# mclon_nano_0_0001.net
KiCad netlist of a schematic drawn in EAGLE
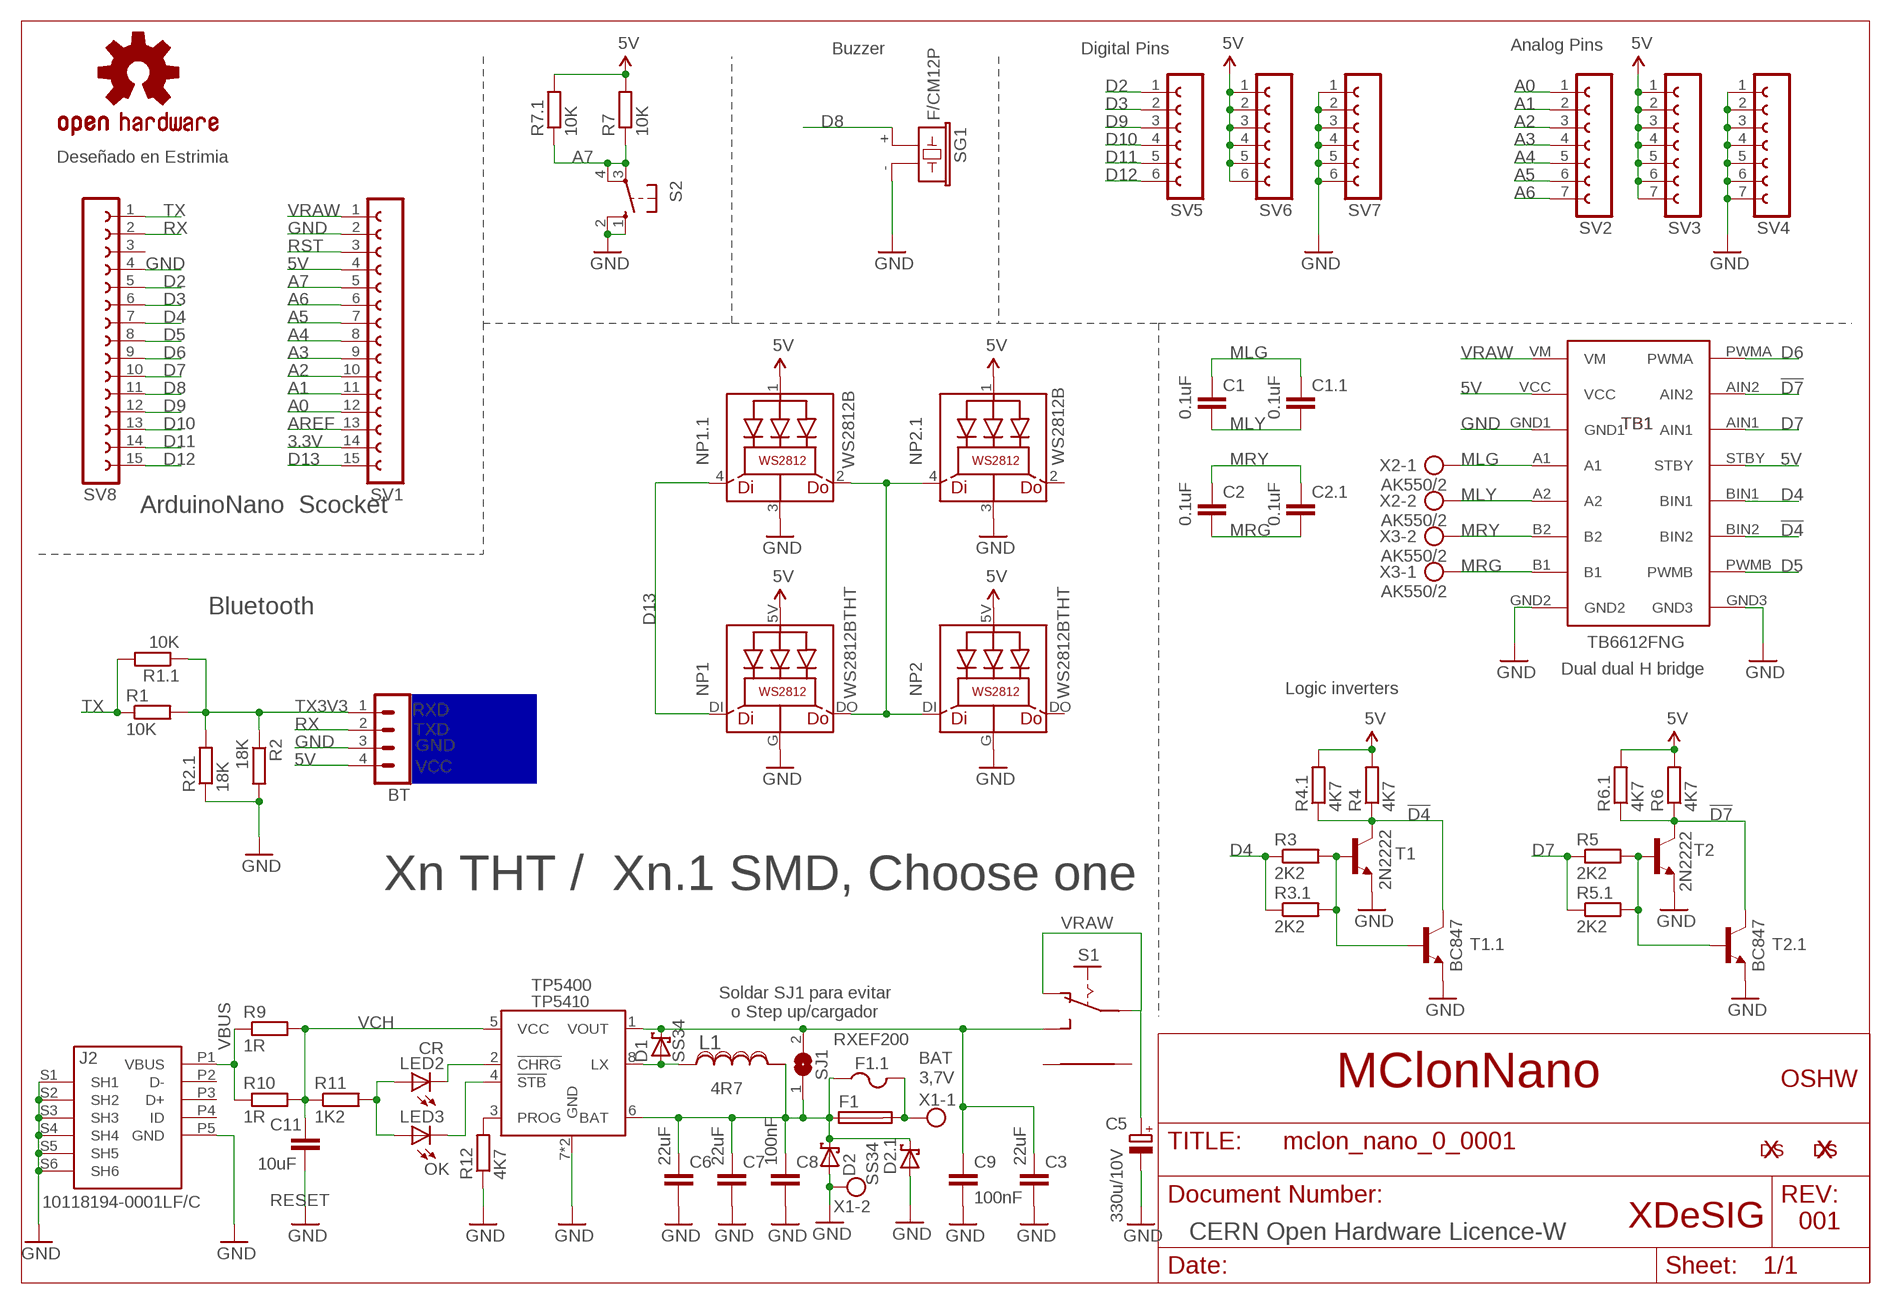
[diagram p0: schematic, sheet 1]

(export (version "E")
  (design (tool "Eeschema 10.0.6"))
  (components
    (comp (ref "BT")
      (value "MA04-1")
      (footprint "eagle-import:MA04-1")
      (libsource (lib "eagle-import") (part "MA04-1"))
    )
    (comp (ref "C1")
      (value "0.1uF")
      (footprint "eagle-import:C050-024X044")
      (libsource (lib "eagle-import") (part "C-EU050-024X044"))
    )
    (comp (ref "C1.1")
      (value "0.1uF")
      (footprint "eagle-import:C1206")
      (libsource (lib "eagle-import") (part "C-EUC1206"))
    )
    (comp (ref "C2")
      (value "0.1uF")
      (footprint "eagle-import:C050-024X044")
      (libsource (lib "eagle-import") (part "C-EU050-024X044"))
    )
    (comp (ref "C2.1")
      (value "0.1uF")
      (footprint "eagle-import:C1206")
      (libsource (lib "eagle-import") (part "C-EUC1206"))
    )
    (comp (ref "C3")
      (value "22uF")
      (footprint "eagle-import:C1206")
      (libsource (lib "eagle-import") (part "C-EUC1206"))
    )
    (comp (ref "C5")
      (value "330u/10V")
      (footprint "eagle-import:E2,5-6")
      (libsource (lib "eagle-import") (part "CPOL-EUE2.5-6"))
    )
    (comp (ref "C6")
      (value "22uF")
      (footprint "eagle-import:C1206")
      (libsource (lib "eagle-import") (part "C-EUC1206"))
    )
    (comp (ref "C7")
      (value "22uF")
      (footprint "eagle-import:C1206")
      (libsource (lib "eagle-import") (part "C-EUC1206"))
    )
    (comp (ref "C8")
      (value "100nF")
      (footprint "eagle-import:C1206")
      (libsource (lib "eagle-import") (part "C-EUC1206"))
    )
    (comp (ref "C9")
      (value "100nF")
      (footprint "eagle-import:C1206")
      (libsource (lib "eagle-import") (part "C-EUC1206"))
    )
    (comp (ref "C11")
      (value "10uF")
      (footprint "eagle-import:C1206")
      (libsource (lib "eagle-import") (part "C-EUC1206"))
    )
    (comp (ref "D1")
      (value "SS34")
      (footprint "eagle-import:DIODE_SMA")
      (libsource (lib "eagle-import") (part "DIODE_SCHOTTKY-DIODESMA"))
    )
    (comp (ref "D2")
      (value "SS34")
      (footprint "eagle-import:DIODE_SMA")
      (libsource (lib "eagle-import") (part "DIODE_SCHOTTKY-DIODESMA"))
    )
    (comp (ref "D2.1")
      (value "SCHOTTKY-DIODEDO35-7")
      (footprint "eagle-import:DO35-7")
      (libsource (lib "eagle-import") (part "SCHOTTKY-DIODEDO35-7"))
    )
    (comp (ref "F1")
      (value "RXEF200")
      (footprint "eagle-import:TE5")
      (libsource (lib "eagle-import") (part "FUSETE5"))
    )
    (comp (ref "F1.1")
      (value "MF-NSMF200")
      (footprint "eagle-import:1812")
      (libsource (lib "eagle-import") (part "PTCFUSE-1812"))
    )
    (comp (ref "J2")
      (value "10118194-0001LF/C")
      (footprint "eagle-import:SMARTPRJ_CON2_USB_MICRO_B_AT")
      (libsource (lib "eagle-import") (part "SMARTPRJ_MYCON2_USB-MINI-B"))
    )
    (comp (ref "L1")
      (value "4R7")
      (footprint "eagle-import:SRN6045")
      (fields (field (name "MF") "Bourns") (field (name "MP") "SRN6045-330M"))
      (libsource (lib "eagle-import") (part "SRN6045-330M6045"))
    )
    (comp (ref "LED2")
      (value "CR")
      (footprint "eagle-import:CHIPLED_0805")
      (libsource (lib "eagle-import") (part "LEDCHIPLED_0805"))
    )
    (comp (ref "LED3")
      (value "OK")
      (footprint "eagle-import:CHIPLED_0805")
      (libsource (lib "eagle-import") (part "LEDCHIPLED_0805"))
    )
    (comp (ref "LOGO4")
      (value "OSHW-LOGOS")
      (footprint "eagle-import:OSHW-LOGO-S")
      (libsource (lib "eagle-import") (part "OSHW-LOGOS"))
    )
    (comp (ref "NP1")
      (value "WS2812BTHT")
      (footprint "eagle-import:NEOPIXEL5MM")
      (libsource (lib "eagle-import") (part "WS2812BTHT"))
    )
    (comp (ref "NP1.1")
      (value "WS2812B")
      (footprint "eagle-import:5050-4")
      (libsource (lib "eagle-import") (part "WS2812B"))
    )
    (comp (ref "NP2")
      (value "WS2812BTHT")
      (footprint "eagle-import:NEOPIXEL5MM")
      (libsource (lib "eagle-import") (part "WS2812BTHT"))
    )
    (comp (ref "NP2.1")
      (value "WS2812B")
      (footprint "eagle-import:5050-4")
      (libsource (lib "eagle-import") (part "WS2812B"))
    )
    (comp (ref "R1")
      (value "10K")
      (footprint "eagle-import:0204_7")
      (libsource (lib "eagle-import") (part "R-EU_0204/7"))
    )
    (comp (ref "R1.1")
      (value "10K")
      (footprint "eagle-import:R1206")
      (libsource (lib "eagle-import") (part "R-EU_R1206"))
    )
    (comp (ref "R2")
      (value "18K")
      (footprint "eagle-import:0204_7")
      (libsource (lib "eagle-import") (part "R-EU_0204/7"))
    )
    (comp (ref "R2.1")
      (value "18K")
      (footprint "eagle-import:R1206")
      (libsource (lib "eagle-import") (part "R-EU_R1206"))
    )
    (comp (ref "R3")
      (value "2K2")
      (footprint "eagle-import:0204_7")
      (libsource (lib "eagle-import") (part "R-EU_0204/7"))
    )
    (comp (ref "R3.1")
      (value "2K2")
      (footprint "eagle-import:R1206")
      (libsource (lib "eagle-import") (part "R-EU_R1206"))
    )
    (comp (ref "R4")
      (value "4K7")
      (footprint "eagle-import:0204_7")
      (libsource (lib "eagle-import") (part "R-EU_0204/7"))
    )
    (comp (ref "R4.1")
      (value "4K7")
      (footprint "eagle-import:R1206")
      (libsource (lib "eagle-import") (part "R-EU_R1206"))
    )
    (comp (ref "R5")
      (value "2K2")
      (footprint "eagle-import:0204_7")
      (libsource (lib "eagle-import") (part "R-EU_0204/7"))
    )
    (comp (ref "R5.1")
      (value "2K2")
      (footprint "eagle-import:R1206")
      (libsource (lib "eagle-import") (part "R-EU_R1206"))
    )
    (comp (ref "R6")
      (value "4K7")
      (footprint "eagle-import:0204_7")
      (libsource (lib "eagle-import") (part "R-EU_0204/7"))
    )
    (comp (ref "R6.1")
      (value "4K7")
      (footprint "eagle-import:R1206")
      (libsource (lib "eagle-import") (part "R-EU_R1206"))
    )
    (comp (ref "R7")
      (value "10K")
      (footprint "eagle-import:0204_7")
      (libsource (lib "eagle-import") (part "R-EU_0204/7"))
    )
    (comp (ref "R7.1")
      (value "10K")
      (footprint "eagle-import:R1206")
      (libsource (lib "eagle-import") (part "R-EU_R1206"))
    )
    (comp (ref "R9")
      (value "1R")
      (footprint "eagle-import:M1206")
      (libsource (lib "eagle-import") (part "R-EU_M1206"))
    )
    (comp (ref "R10")
      (value "1R")
      (footprint "eagle-import:M1206")
      (libsource (lib "eagle-import") (part "R-EU_M1206"))
    )
    (comp (ref "R11")
      (value "1K2")
      (footprint "eagle-import:R1206")
      (libsource (lib "eagle-import") (part "R-EU_R1206"))
    )
    (comp (ref "R12")
      (value "4K7")
      (footprint "eagle-import:R1206")
      (libsource (lib "eagle-import") (part "R-EU_R1206"))
    )
    (comp (ref "S1")
      (value "ESCORNA_SK12F14D")
      (footprint "eagle-import:ESCORNA_SK-12D07")
      (libsource (lib "eagle-import") (part "ESCORNA_SK12F14D"))
    )
    (comp (ref "S2")
      (value "10-XX")
      (footprint "eagle-import:B3F-10XX")
      (fields (field (name "MPN") "B3F-1000"))
      (libsource (lib "eagle-import") (part "10-XX"))
    )
    (comp (ref "SG1")
      (value "F/CM12P")
      (footprint "eagle-import:F_CM12P")
      (libsource (lib "eagle-import") (part "F/CM12P"))
    )
    (comp (ref "SJ1")
      (value "JUMPER_SJW")
      (footprint "eagle-import:JUMPER_SJW")
      (libsource (lib "eagle-import") (part "JUMPER_SJW"))
    )
    (comp (ref "SV1")
      (value "CON-LSTA_FE15-1")
      (footprint "eagle-import:CON-LSTA_FE15")
      (libsource (lib "eagle-import") (part "CON-LSTA_FE15-1"))
    )
    (comp (ref "SV2")
      (value "FE07-1")
      (footprint "eagle-import:FE07")
      (libsource (lib "eagle-import") (part "FE07-1"))
    )
    (comp (ref "SV3")
      (value "FE07-1")
      (footprint "eagle-import:FE07")
      (libsource (lib "eagle-import") (part "FE07-1"))
    )
    (comp (ref "SV4")
      (value "FE07-1")
      (footprint "eagle-import:FE07")
      (libsource (lib "eagle-import") (part "FE07-1"))
    )
    (comp (ref "SV5")
      (value "FE06-1")
      (footprint "eagle-import:FE06")
      (libsource (lib "eagle-import") (part "FE06-1"))
    )
    (comp (ref "SV6")
      (value "FE06-1")
      (footprint "eagle-import:FE06")
      (libsource (lib "eagle-import") (part "FE06-1"))
    )
    (comp (ref "SV7")
      (value "FE06-1")
      (footprint "eagle-import:FE06")
      (libsource (lib "eagle-import") (part "FE06-1"))
    )
    (comp (ref "SV8")
      (value "CON-LSTA_FE15-1")
      (footprint "eagle-import:CON-LSTA_FE15")
      (libsource (lib "eagle-import") (part "CON-LSTA_FE15-1"))
    )
    (comp (ref "T1")
      (value "2N2222")
      (footprint "eagle-import:TO92-EBC-OVAL")
      (libsource (lib "eagle-import") (part "2N2222"))
    )
    (comp (ref "T1.1")
      (value "BC847")
      (footprint "eagle-import:SOT23")
      (libsource (lib "eagle-import") (part "BC847"))
    )
    (comp (ref "T2")
      (value "2N2222")
      (footprint "eagle-import:TO92-EBC-OVAL")
      (libsource (lib "eagle-import") (part "2N2222"))
    )
    (comp (ref "T2.1")
      (value "BC847")
      (footprint "eagle-import:SOT23")
      (libsource (lib "eagle-import") (part "BC847"))
    )
    (comp (ref "TB1")
      (value "TB6612FNG")
      (footprint "eagle-import:TB6612FNG")
      (libsource (lib "eagle-import") (part "TB6612FNG"))
    )
    (comp (ref "U$7")
      (value "OSHW")
      (footprint "eagle-import:OSHW")
      (libsource (lib "eagle-import") (part "OSHW"))
    )
    (comp (ref "U$8")
      (value "XDESIG5MM")
      (footprint "eagle-import:XDESIG_CU")
      (libsource (lib "eagle-import") (part "XDESIG5MM"))
    )
    (comp (ref "U$18")
      (value "XDESIG21")
      (footprint "eagle-import:XDESIG")
      (libsource (lib "eagle-import") (part "XDESIG21"))
    )
    (comp (ref "U$19")
      (value "XDESIG5MM")
      (footprint "eagle-import:XDESIG_CU")
      (libsource (lib "eagle-import") (part "XDESIG5MM"))
    )
    (comp (ref "U1")
      (value "TP5400")
      (footprint "eagle-import:ESOP8")
      (libsource (lib "eagle-import") (part "TP5400"))
    )
    (comp (ref "X1")
      (value "AK550/2")
      (footprint "eagle-import:AK550_2")
      (libsource (lib "eagle-import") (part "AK550/2"))
    )
    (comp (ref "X2")
      (value "AK550/2")
      (footprint "eagle-import:AK550_2")
      (libsource (lib "eagle-import") (part "AK550/2"))
    )
    (comp (ref "X3")
      (value "AK550/2")
      (footprint "eagle-import:AK550_2")
      (libsource (lib "eagle-import") (part "AK550/2"))
    )
  )
  (nets
    (net (code "1") (name "/3.3V") (class "Default")
      (node (ref "SV1") (pin "14") (pinfunction "14_14") (pintype "passive"))
    )
    (net (code "2") (name "/A0") (class "Default")
      (node (ref "SV1") (pin "12") (pinfunction "12_12") (pintype "passive"))
      (node (ref "SV2") (pin "1") (pinfunction "1_1") (pintype "passive"))
    )
    (net (code "3") (name "/A1") (class "Default")
      (node (ref "SV1") (pin "11") (pinfunction "11_11") (pintype "passive"))
      (node (ref "SV2") (pin "2") (pinfunction "2_2") (pintype "passive"))
    )
    (net (code "4") (name "/A2") (class "Default")
      (node (ref "SV1") (pin "10") (pinfunction "10_10") (pintype "passive"))
      (node (ref "SV2") (pin "3") (pinfunction "3_3") (pintype "passive"))
    )
    (net (code "5") (name "/A3") (class "Default")
      (node (ref "SV1") (pin "9") (pinfunction "9_9") (pintype "passive"))
      (node (ref "SV2") (pin "4") (pinfunction "4_4") (pintype "passive"))
    )
    (net (code "6") (name "/A4") (class "Default")
      (node (ref "SV1") (pin "8") (pinfunction "8_8") (pintype "passive"))
      (node (ref "SV2") (pin "5") (pinfunction "5_5") (pintype "passive"))
    )
    (net (code "7") (name "/A5") (class "Default")
      (node (ref "SV1") (pin "7") (pinfunction "7_7") (pintype "passive"))
      (node (ref "SV2") (pin "6") (pinfunction "6_6") (pintype "passive"))
    )
    (net (code "8") (name "/A6") (class "Default")
      (node (ref "SV1") (pin "6") (pinfunction "6_6") (pintype "passive"))
      (node (ref "SV2") (pin "7") (pinfunction "7_7") (pintype "passive"))
    )
    (net (code "9") (name "/A7") (class "Default")
      (node (ref "R7") (pin "1") (pinfunction "1_1") (pintype "passive"))
      (node (ref "R7.1") (pin "1") (pinfunction "1_1") (pintype "passive"))
      (node (ref "S2") (pin "3") (pinfunction "P_3") (pintype "passive"))
      (node (ref "S2") (pin "4") (pinfunction "P1_4") (pintype "passive"))
      (node (ref "SV1") (pin "5") (pinfunction "5_5") (pintype "passive"))
    )
    (net (code "10") (name "/AREF") (class "Default")
      (node (ref "SV1") (pin "13") (pinfunction "13_13") (pintype "passive"))
    )
    (net (code "11") (name "/BAT") (class "Default")
      (node (ref "C6") (pin "1") (pinfunction "1_1") (pintype "passive"))
      (node (ref "C7") (pin "1") (pinfunction "1_1") (pintype "passive"))
      (node (ref "C8") (pin "1") (pinfunction "1_1") (pintype "passive"))
      (node (ref "D2") (pin "C") (pinfunction "C_C") (pintype "passive"))
      (node (ref "D2.1") (pin "C") (pinfunction "C_C") (pintype "passive"))
      (node (ref "F1") (pin "1") (pinfunction "1_1") (pintype "passive"))
      (node (ref "F1.1") (pin "1") (pinfunction "1_1") (pintype "passive"))
      (node (ref "L1") (pin "1") (pinfunction "1_1") (pintype "passive"))
      (node (ref "SJ1") (pin "1") (pinfunction "1_1") (pintype "passive"))
      (node (ref "U1") (pin "6") (pinfunction "BAT_6") (pintype "bidirectional"))
    )
    (net (code "12") (name "/D2") (class "Default")
      (node (ref "SV5") (pin "1") (pinfunction "1_1") (pintype "passive"))
      (node (ref "SV8") (pin "5") (pinfunction "5_5") (pintype "passive"))
    )
    (net (code "13") (name "/D3") (class "Default")
      (node (ref "SV5") (pin "2") (pinfunction "2_2") (pintype "passive"))
      (node (ref "SV8") (pin "6") (pinfunction "6_6") (pintype "passive"))
    )
    (net (code "14") (name "/D4") (class "Default")
      (node (ref "R3") (pin "1") (pinfunction "1_1") (pintype "passive"))
      (node (ref "R3.1") (pin "1") (pinfunction "1_1") (pintype "passive"))
      (node (ref "SV8") (pin "7") (pinfunction "7_7") (pintype "passive"))
      (node (ref "TB1") (pin "BIN1") (pinfunction "BIN1_BIN1") (pintype "bidirectional"))
    )
    (net (code "15") (name "/D5") (class "Default")
      (node (ref "SV8") (pin "8") (pinfunction "8_8") (pintype "passive"))
      (node (ref "TB1") (pin "PWMB") (pinfunction "PWMB_PWMB") (pintype "bidirectional"))
    )
    (net (code "16") (name "/D6") (class "Default")
      (node (ref "SV8") (pin "9") (pinfunction "9_9") (pintype "passive"))
      (node (ref "TB1") (pin "PWMA") (pinfunction "PWMA_PWMA") (pintype "bidirectional"))
    )
    (net (code "17") (name "/D7") (class "Default")
      (node (ref "R5") (pin "1") (pinfunction "1_1") (pintype "passive"))
      (node (ref "R5.1") (pin "1") (pinfunction "1_1") (pintype "passive"))
      (node (ref "SV8") (pin "10") (pinfunction "10_10") (pintype "passive"))
      (node (ref "TB1") (pin "AIN1") (pinfunction "AIN1_AIN1") (pintype "bidirectional"))
    )
    (net (code "18") (name "/D8") (class "Default")
      (node (ref "SG1") (pin "+") (pinfunction "1_+") (pintype "passive"))
      (node (ref "SV8") (pin "11") (pinfunction "11_11") (pintype "passive"))
    )
    (net (code "19") (name "/D9") (class "Default")
      (node (ref "SV5") (pin "3") (pinfunction "3_3") (pintype "passive"))
      (node (ref "SV8") (pin "12") (pinfunction "12_12") (pintype "passive"))
    )
    (net (code "20") (name "/D10") (class "Default")
      (node (ref "SV5") (pin "4") (pinfunction "4_4") (pintype "passive"))
      (node (ref "SV8") (pin "13") (pinfunction "13_13") (pintype "passive"))
    )
    (net (code "21") (name "/D11") (class "Default")
      (node (ref "SV5") (pin "5") (pinfunction "5_5") (pintype "passive"))
      (node (ref "SV8") (pin "14") (pinfunction "14_14") (pintype "passive"))
    )
    (net (code "22") (name "/D12") (class "Default")
      (node (ref "SV5") (pin "6") (pinfunction "6_6") (pintype "passive"))
      (node (ref "SV8") (pin "15") (pinfunction "15_15") (pintype "passive"))
    )
    (net (code "23") (name "/D13") (class "Default")
      (node (ref "NP1") (pin "DI") (pinfunction "DI_DI") (pintype "input"))
      (node (ref "NP1.1") (pin "4") (pinfunction "DI_4") (pintype "input"))
      (node (ref "SV1") (pin "15") (pinfunction "15_15") (pintype "passive"))
    )
    (net (code "24") (name "/MLG") (class "Default")
      (node (ref "C1") (pin "1") (pinfunction "1_1") (pintype "passive"))
      (node (ref "C1.1") (pin "1") (pinfunction "1_1") (pintype "passive"))
      (node (ref "TB1") (pin "A1") (pinfunction "A1_A1") (pintype "bidirectional"))
      (node (ref "X2") (pin "1") (pinfunction "KL_1") (pintype "passive"))
    )
    (net (code "25") (name "/MLY") (class "Default")
      (node (ref "C1") (pin "2") (pinfunction "2_2") (pintype "passive"))
      (node (ref "C1.1") (pin "2") (pinfunction "2_2") (pintype "passive"))
      (node (ref "TB1") (pin "A2") (pinfunction "A2_A2") (pintype "bidirectional"))
      (node (ref "X2") (pin "2") (pinfunction "KL_2") (pintype "passive"))
    )
    (net (code "26") (name "/MRG") (class "Default")
      (node (ref "C2") (pin "2") (pinfunction "2_2") (pintype "passive"))
      (node (ref "C2.1") (pin "2") (pinfunction "2_2") (pintype "passive"))
      (node (ref "TB1") (pin "B1") (pinfunction "B1_B1") (pintype "bidirectional"))
      (node (ref "X3") (pin "1") (pinfunction "KL_1") (pintype "passive"))
    )
    (net (code "27") (name "/MRY") (class "Default")
      (node (ref "C2") (pin "1") (pinfunction "1_1") (pintype "passive"))
      (node (ref "C2.1") (pin "1") (pinfunction "1_1") (pintype "passive"))
      (node (ref "TB1") (pin "B2") (pinfunction "B2_B2") (pintype "bidirectional"))
      (node (ref "X3") (pin "2") (pinfunction "KL_2") (pintype "passive"))
    )
    (net (code "29") (name "/RST") (class "Default")
      (node (ref "SV1") (pin "3") (pinfunction "3_3") (pintype "passive"))
    )
    (net (code "30") (name "/RX") (class "Default")
      (node (ref "BT") (pin "2") (pinfunction "2_2") (pintype "passive"))
      (node (ref "SV8") (pin "2") (pinfunction "2_2") (pintype "passive"))
    )
    (net (code "31") (name "/TX") (class "Default")
      (node (ref "R1") (pin "1") (pinfunction "1_1") (pintype "passive"))
      (node (ref "R1.1") (pin "2") (pinfunction "2_2") (pintype "passive"))
      (node (ref "SV8") (pin "1") (pinfunction "1_1") (pintype "passive"))
    )
    (net (code "32") (name "/TX3V3") (class "Default")
      (node (ref "BT") (pin "1") (pinfunction "1_1") (pintype "passive"))
      (node (ref "R1") (pin "2") (pinfunction "2_2") (pintype "passive"))
      (node (ref "R1.1") (pin "1") (pinfunction "1_1") (pintype "passive"))
      (node (ref "R2") (pin "1") (pinfunction "1_1") (pintype "passive"))
      (node (ref "R2.1") (pin "2") (pinfunction "2_2") (pintype "passive"))
    )
    (net (code "33") (name "/VBUS") (class "Default")
      (node (ref "J2") (pin "P1") (pinfunction "VBUS_P1") (pintype "power_in"))
      (node (ref "R10") (pin "1") (pinfunction "1_1") (pintype "passive"))
      (node (ref "R9") (pin "1") (pinfunction "1_1") (pintype "passive"))
    )
    (net (code "34") (name "/VCH") (class "Default")
      (node (ref "C11") (pin "1") (pinfunction "1_1") (pintype "passive"))
      (node (ref "R10") (pin "2") (pinfunction "2_2") (pintype "passive"))
      (node (ref "R11") (pin "1") (pinfunction "1_1") (pintype "passive"))
      (node (ref "R9") (pin "2") (pinfunction "2_2") (pintype "passive"))
      (node (ref "U1") (pin "5") (pinfunction "VCC_5") (pintype "power_in"))
    )
    (net (code "35") (name "/VRAW") (class "Default")
      (node (ref "C5") (pin "+") (pinfunction "+_+") (pintype "passive"))
      (node (ref "S1") (pin "P$1") (pinfunction "P_P$1") (pintype "passive"))
      (node (ref "S1") (pin "P$2") (pinfunction "O_P$2") (pintype "passive"))
      (node (ref "SV1") (pin "1") (pinfunction "1_1") (pintype "passive"))
      (node (ref "TB1") (pin "VM") (pinfunction "VM_VM") (pintype "bidirectional"))
    )
    (net (code "36") (name "/~{D4}") (class "Default")
      (node (ref "R4") (pin "1") (pinfunction "1_1") (pintype "passive"))
      (node (ref "R4.1") (pin "1") (pinfunction "1_1") (pintype "passive"))
      (node (ref "T1") (pin "C") (pinfunction "C_C") (pintype "passive"))
      (node (ref "T1.1") (pin "3") (pinfunction "C_3") (pintype "passive"))
      (node (ref "TB1") (pin "BIN2") (pinfunction "BIN2_BIN2") (pintype "bidirectional"))
    )
    (net (code "37") (name "/~{D7}") (class "Default")
      (node (ref "R6") (pin "1") (pinfunction "1_1") (pintype "passive"))
      (node (ref "R6.1") (pin "1") (pinfunction "1_1") (pintype "passive"))
      (node (ref "T2") (pin "C") (pinfunction "C_C") (pintype "passive"))
      (node (ref "T2.1") (pin "3") (pinfunction "C_3") (pintype "passive"))
      (node (ref "TB1") (pin "AIN2") (pinfunction "AIN2_AIN2") (pintype "bidirectional"))
    )
    (net (code "38") (name "5V") (class "Default")
      (node (ref "BT") (pin "4") (pinfunction "4_4") (pintype "passive"))
      (node (ref "NP1") (pin "5V") (pinfunction "LEDVDD_5V") (pintype "power_in"))
      (node (ref "NP1.1") (pin "1") (pinfunction "LEDVDD_1") (pintype "power_in"))
      (node (ref "NP2") (pin "5V") (pinfunction "LEDVDD_5V") (pintype "power_in"))
      (node (ref "NP2.1") (pin "1") (pinfunction "LEDVDD_1") (pintype "power_in"))
      (node (ref "R4") (pin "2") (pinfunction "2_2") (pintype "passive"))
      (node (ref "R4.1") (pin "2") (pinfunction "2_2") (pintype "passive"))
      (node (ref "R6") (pin "2") (pinfunction "2_2") (pintype "passive"))
      (node (ref "R6.1") (pin "2") (pinfunction "2_2") (pintype "passive"))
      (node (ref "R7") (pin "2") (pinfunction "2_2") (pintype "passive"))
      (node (ref "R7.1") (pin "2") (pinfunction "2_2") (pintype "passive"))
      (node (ref "SV1") (pin "4") (pinfunction "4_4") (pintype "passive"))
      (node (ref "SV3") (pin "1") (pinfunction "1_1") (pintype "passive"))
      (node (ref "SV3") (pin "2") (pinfunction "2_2") (pintype "passive"))
      (node (ref "SV3") (pin "3") (pinfunction "3_3") (pintype "passive"))
      (node (ref "SV3") (pin "4") (pinfunction "4_4") (pintype "passive"))
      (node (ref "SV3") (pin "5") (pinfunction "5_5") (pintype "passive"))
      (node (ref "SV3") (pin "6") (pinfunction "6_6") (pintype "passive"))
      (node (ref "SV3") (pin "7") (pinfunction "7_7") (pintype "passive"))
      (node (ref "SV6") (pin "1") (pinfunction "1_1") (pintype "passive"))
      (node (ref "SV6") (pin "2") (pinfunction "2_2") (pintype "passive"))
      (node (ref "SV6") (pin "3") (pinfunction "3_3") (pintype "passive"))
      (node (ref "SV6") (pin "4") (pinfunction "4_4") (pintype "passive"))
      (node (ref "SV6") (pin "5") (pinfunction "5_5") (pintype "passive"))
      (node (ref "SV6") (pin "6") (pinfunction "6_6") (pintype "passive"))
      (node (ref "TB1") (pin "STBY") (pinfunction "STBY_STBY") (pintype "bidirectional"))
      (node (ref "TB1") (pin "VCC") (pinfunction "VCC_VCC") (pintype "bidirectional"))
    )
    (net (code "39") (name "GND") (class "Default")
      (node (ref "BT") (pin "3") (pinfunction "3_3") (pintype "passive"))
      (node (ref "C11") (pin "2") (pinfunction "2_2") (pintype "passive"))
      (node (ref "C3") (pin "2") (pinfunction "2_2") (pintype "passive"))
      (node (ref "C5") (pin "-") (pinfunction "-_-") (pintype "passive"))
      (node (ref "C6") (pin "2") (pinfunction "2_2") (pintype "passive"))
      (node (ref "C7") (pin "2") (pinfunction "2_2") (pintype "passive"))
      (node (ref "C8") (pin "2") (pinfunction "2_2") (pintype "passive"))
      (node (ref "C9") (pin "2") (pinfunction "2_2") (pintype "passive"))
      (node (ref "D2") (pin "A") (pinfunction "A_A") (pintype "passive"))
      (node (ref "D2.1") (pin "A") (pinfunction "A_A") (pintype "passive"))
      (node (ref "J2") (pin "P5") (pinfunction "GND_P5") (pintype "passive"))
      (node (ref "J2") (pin "S1") (pinfunction "SH1_S1") (pintype "passive"))
      (node (ref "J2") (pin "S2") (pinfunction "SH2_S2") (pintype "passive"))
      (node (ref "J2") (pin "S3") (pinfunction "SH3_S3") (pintype "passive"))
      (node (ref "J2") (pin "S4") (pinfunction "SH4_S4") (pintype "passive"))
      (node (ref "J2") (pin "S5") (pinfunction "SH5_S5") (pintype "passive"))
      (node (ref "J2") (pin "S6") (pinfunction "SH6_S6") (pintype "passive"))
      (node (ref "NP1") (pin "G") (pinfunction "GND_G") (pintype "power_in"))
      (node (ref "NP1.1") (pin "3") (pinfunction "GND_3") (pintype "power_in"))
      (node (ref "NP2") (pin "G") (pinfunction "GND_G") (pintype "power_in"))
      (node (ref "NP2.1") (pin "3") (pinfunction "GND_3") (pintype "power_in"))
      (node (ref "R12") (pin "1") (pinfunction "1_1") (pintype "passive"))
      (node (ref "R2") (pin "2") (pinfunction "2_2") (pintype "passive"))
      (node (ref "R2.1") (pin "1") (pinfunction "1_1") (pintype "passive"))
      (node (ref "S2") (pin "1") (pinfunction "S_1") (pintype "passive"))
      (node (ref "S2") (pin "2") (pinfunction "S1_2") (pintype "passive"))
      (node (ref "SG1") (pin "-") (pinfunction "2_-") (pintype "passive"))
      (node (ref "SV1") (pin "2") (pinfunction "2_2") (pintype "passive"))
      (node (ref "SV4") (pin "1") (pinfunction "1_1") (pintype "passive"))
      (node (ref "SV4") (pin "2") (pinfunction "2_2") (pintype "passive"))
      (node (ref "SV4") (pin "3") (pinfunction "3_3") (pintype "passive"))
      (node (ref "SV4") (pin "4") (pinfunction "4_4") (pintype "passive"))
      (node (ref "SV4") (pin "5") (pinfunction "5_5") (pintype "passive"))
      (node (ref "SV4") (pin "6") (pinfunction "6_6") (pintype "passive"))
      (node (ref "SV4") (pin "7") (pinfunction "7_7") (pintype "passive"))
      (node (ref "SV7") (pin "1") (pinfunction "1_1") (pintype "passive"))
      (node (ref "SV7") (pin "2") (pinfunction "2_2") (pintype "passive"))
      (node (ref "SV7") (pin "3") (pinfunction "3_3") (pintype "passive"))
      (node (ref "SV7") (pin "4") (pinfunction "4_4") (pintype "passive"))
      (node (ref "SV7") (pin "5") (pinfunction "5_5") (pintype "passive"))
      (node (ref "SV7") (pin "6") (pinfunction "6_6") (pintype "passive"))
      (node (ref "SV8") (pin "4") (pinfunction "4_4") (pintype "passive"))
      (node (ref "T1") (pin "E") (pinfunction "E_E") (pintype "passive"))
      (node (ref "T1.1") (pin "2") (pinfunction "E_2") (pintype "passive"))
      (node (ref "T2") (pin "E") (pinfunction "E_E") (pintype "passive"))
      (node (ref "T2.1") (pin "2") (pinfunction "E_2") (pintype "passive"))
      (node (ref "TB1") (pin "GND1") (pinfunction "GND1_GND1") (pintype "bidirectional"))
      (node (ref "TB1") (pin "GND2") (pinfunction "GND2_GND2") (pintype "bidirectional"))
      (node (ref "TB1") (pin "GND3") (pinfunction "GND3_GND3") (pintype "bidirectional"))
      (node (ref "U1") (pin "7") (pinfunction "GND_7") (pintype "power_in"))
      (node (ref "U1") (pin "9") (pinfunction "GND_9") (pintype "power_in"))
      (node (ref "X1") (pin "2") (pinfunction "KL_2") (pintype "passive"))
    )
    (net (code "40") (name "Net-(LED2-PadA)") (class "Default")
      (node (ref "LED2") (pin "A") (pinfunction "A_A") (pintype "passive"))
      (node (ref "LED3") (pin "A") (pinfunction "A_A") (pintype "passive"))
      (node (ref "R11") (pin "2") (pinfunction "2_2") (pintype "passive"))
    )
    (net (code "41") (name "Net-(NP1.1-DO)") (class "Default")
      (node (ref "NP1") (pin "DO") (pinfunction "DO_DO") (pintype "output"))
      (node (ref "NP1.1") (pin "2") (pinfunction "DO_2") (pintype "output"))
      (node (ref "NP2") (pin "DI") (pinfunction "DI_DI") (pintype "input"))
      (node (ref "NP2.1") (pin "4") (pinfunction "DI_4") (pintype "input"))
    )
    (net (code "42") (name "Net-(S1-S)") (class "Default")
      (node (ref "C3") (pin "1") (pinfunction "1_1") (pintype "passive"))
      (node (ref "C9") (pin "1") (pinfunction "1_1") (pintype "passive"))
      (node (ref "D1") (pin "C") (pinfunction "C_C") (pintype "passive"))
      (node (ref "S1") (pin "P$3") (pinfunction "S_P$3") (pintype "passive"))
      (node (ref "SJ1") (pin "2") (pinfunction "2_2") (pintype "passive"))
      (node (ref "U1") (pin "1") (pinfunction "VOUT_1") (pintype "power_in"))
    )
    (net (code "43") (name "Net-(T1.1-B)") (class "Default")
      (node (ref "R3") (pin "2") (pinfunction "2_2") (pintype "passive"))
      (node (ref "R3.1") (pin "2") (pinfunction "2_2") (pintype "passive"))
      (node (ref "T1") (pin "B") (pinfunction "B_B") (pintype "passive"))
      (node (ref "T1.1") (pin "1") (pinfunction "B_1") (pintype "passive"))
    )
    (net (code "44") (name "Net-(T2.1-B)") (class "Default")
      (node (ref "R5") (pin "2") (pinfunction "2_2") (pintype "passive"))
      (node (ref "R5.1") (pin "2") (pinfunction "2_2") (pintype "passive"))
      (node (ref "T2") (pin "B") (pinfunction "B_B") (pintype "passive"))
      (node (ref "T2.1") (pin "1") (pinfunction "B_1") (pintype "passive"))
    )
    (net (code "45") (name "Net-(U1-LX)") (class "Default")
      (node (ref "D1") (pin "A") (pinfunction "A_A") (pintype "passive"))
      (node (ref "L1") (pin "2") (pinfunction "2_2") (pintype "passive"))
      (node (ref "U1") (pin "8") (pinfunction "LX_8") (pintype "bidirectional"))
    )
    (net (code "46") (name "Net-(U1-PROG)") (class "Default")
      (node (ref "R12") (pin "2") (pinfunction "2_2") (pintype "passive"))
      (node (ref "U1") (pin "3") (pinfunction "PROG_3") (pintype "bidirectional"))
    )
    (net (code "47") (name "Net-(U1-~{CHRG})") (class "Default")
      (node (ref "LED2") (pin "C") (pinfunction "C_C") (pintype "passive"))
      (node (ref "U1") (pin "2") (pinfunction "~{CHRG}_2") (pintype "bidirectional"))
    )
    (net (code "48") (name "Net-(U1-~{STB})") (class "Default")
      (node (ref "LED3") (pin "C") (pinfunction "C_C") (pintype "passive"))
      (node (ref "U1") (pin "4") (pinfunction "~{STB}_4") (pintype "bidirectional"))
    )
    (net (code "49") (name "Net-(X1A-KL)") (class "Default")
      (node (ref "F1") (pin "2") (pinfunction "2_2") (pintype "passive"))
      (node (ref "F1.1") (pin "2") (pinfunction "2_2") (pintype "passive"))
      (node (ref "X1") (pin "1") (pinfunction "KL_1") (pintype "passive"))
    )
    (net (code "50") (name "unconnected-(J2-D+-PadP3)") (class "Default")
      (node (ref "J2") (pin "P3") (pinfunction "D+_P3") (pintype "bidirectional"))
    )
    (net (code "51") (name "unconnected-(J2-D--PadP2)") (class "Default")
      (node (ref "J2") (pin "P2") (pinfunction "D-_P2") (pintype "bidirectional"))
    )
    (net (code "52") (name "unconnected-(J2-ID-PadP4)") (class "Default")
      (node (ref "J2") (pin "P4") (pinfunction "ID_P4") (pintype "bidirectional"))
    )
    (net (code "53") (name "unconnected-(NP2-PadDO)") (class "Default")
      (node (ref "NP2") (pin "DO") (pinfunction "DO_DO") (pintype "output"))
    )
    (net (code "54") (name "unconnected-(NP2.1-DO-Pad2)") (class "Default")
      (node (ref "NP2.1") (pin "2") (pinfunction "DO_2") (pintype "output"))
    )
    (net (code "55") (name "unconnected-(S1-P$1-PadP$4)") (class "Default")
      (node (ref "S1") (pin "P$4") (pinfunction "P$1_P$4") (pintype "passive"))
    )
    (net (code "56") (name "unconnected-(S1-P$2-PadP$5)") (class "Default")
      (node (ref "S1") (pin "P$5") (pinfunction "P$2_P$5") (pintype "bidirectional"))
    )
    (net (code "57") (name "unconnected-(SV8-Pad3)") (class "Default")
      (node (ref "SV8") (pin "3") (pinfunction "3_3") (pintype "passive"))
    )
  )
)
